# Button_Pad_Breakout-v05.net
KiCad netlist of a schematic drawn in Altium Designer
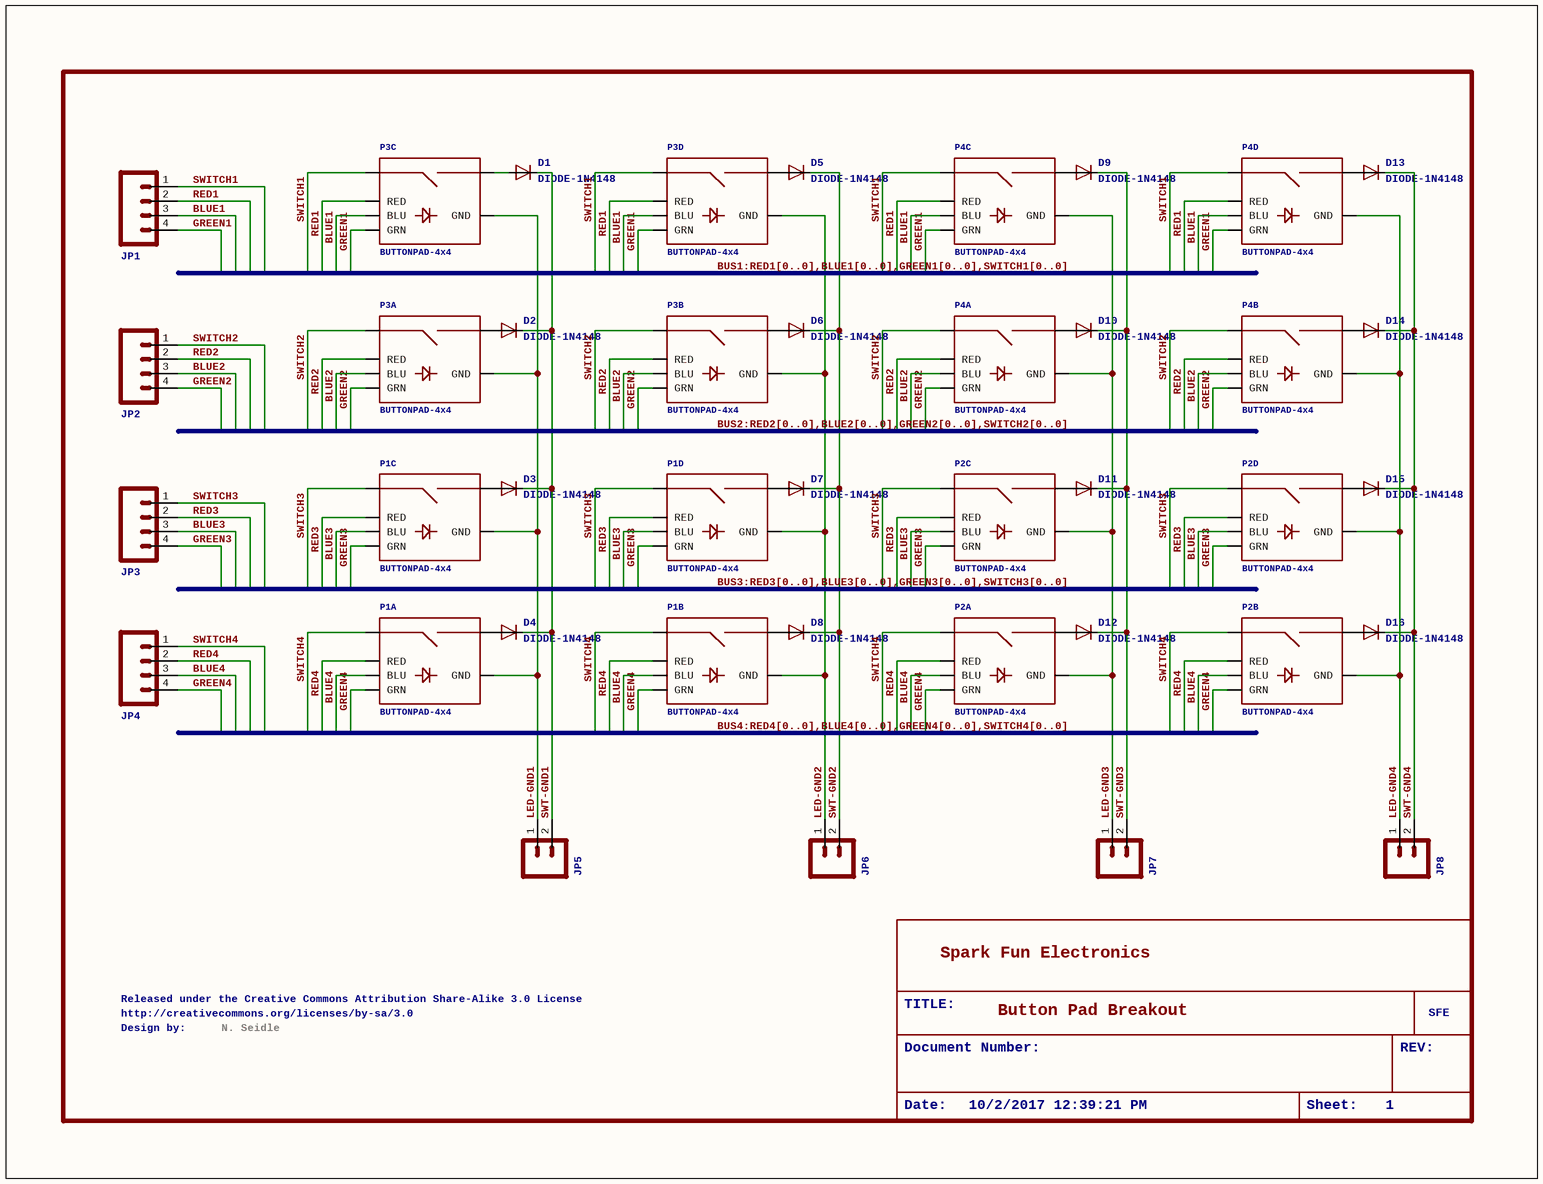
[diagram p0: Button_Pad_Breakout-v05.SchDoc]

(export (version "E")
  (design (tool "Eeschema 10.0.6"))
  (components
    (comp (ref "D1")
      (value "DIODE-1N4148")
      (footprint "DOIDE-1N4148")
      (libsource (lib "SparkFun") (part "DIODE-1N4148"))
    )
    (comp (ref "D2")
      (value "DIODE-1N4148")
      (footprint "DOIDE-1N4148")
      (libsource (lib "SparkFun") (part "DIODE-1N4148"))
    )
    (comp (ref "D3")
      (value "DIODE-1N4148")
      (footprint "DOIDE-1N4148")
      (libsource (lib "SparkFun") (part "DIODE-1N4148"))
    )
    (comp (ref "D4")
      (value "DIODE-1N4148")
      (footprint "DOIDE-1N4148")
      (libsource (lib "SparkFun") (part "DIODE-1N4148"))
    )
    (comp (ref "D5")
      (value "DIODE-1N4148")
      (footprint "DOIDE-1N4148")
      (libsource (lib "SparkFun") (part "DIODE-1N4148"))
    )
    (comp (ref "D6")
      (value "DIODE-1N4148")
      (footprint "DOIDE-1N4148")
      (libsource (lib "SparkFun") (part "DIODE-1N4148"))
    )
    (comp (ref "D7")
      (value "DIODE-1N4148")
      (footprint "DOIDE-1N4148")
      (libsource (lib "SparkFun") (part "DIODE-1N4148"))
    )
    (comp (ref "D8")
      (value "DIODE-1N4148")
      (footprint "DOIDE-1N4148")
      (libsource (lib "SparkFun") (part "DIODE-1N4148"))
    )
    (comp (ref "D9")
      (value "DIODE-1N4148")
      (footprint "DOIDE-1N4148")
      (libsource (lib "SparkFun") (part "DIODE-1N4148"))
    )
    (comp (ref "D10")
      (value "DIODE-1N4148")
      (footprint "DOIDE-1N4148")
      (libsource (lib "SparkFun") (part "DIODE-1N4148"))
    )
    (comp (ref "D11")
      (value "DIODE-1N4148")
      (footprint "DOIDE-1N4148")
      (libsource (lib "SparkFun") (part "DIODE-1N4148"))
    )
    (comp (ref "D12")
      (value "DIODE-1N4148")
      (footprint "DOIDE-1N4148")
      (libsource (lib "SparkFun") (part "DIODE-1N4148"))
    )
    (comp (ref "D13")
      (value "DIODE-1N4148")
      (footprint "DOIDE-1N4148")
      (libsource (lib "SparkFun") (part "DIODE-1N4148"))
    )
    (comp (ref "D14")
      (value "DIODE-1N4148")
      (footprint "DOIDE-1N4148")
      (libsource (lib "SparkFun") (part "DIODE-1N4148"))
    )
    (comp (ref "D15")
      (value "DIODE-1N4148")
      (footprint "DOIDE-1N4148")
      (libsource (lib "SparkFun") (part "DIODE-1N4148"))
    )
    (comp (ref "D16")
      (value "DIODE-1N4148")
      (footprint "DOIDE-1N4148")
      (libsource (lib "SparkFun") (part "DIODE-1N4148"))
    )
    (comp (ref "JP1")
      (value "M04POLAR")
      (footprint "MOLEX-1X4")
      (libsource (lib "SparkFun") (part "M04POLAR"))
    )
    (comp (ref "JP2")
      (value "M04POLAR")
      (footprint "MOLEX-1X4")
      (libsource (lib "SparkFun") (part "M04POLAR"))
    )
    (comp (ref "JP3")
      (value "M04POLAR")
      (footprint "MOLEX-1X4")
      (libsource (lib "SparkFun") (part "M04POLAR"))
    )
    (comp (ref "JP4")
      (value "M04POLAR")
      (footprint "MOLEX-1X4")
      (libsource (lib "SparkFun") (part "M04POLAR"))
    )
    (comp (ref "JP5")
      (value "M02POLAR")
      (footprint "MOLEX-1X2")
      (libsource (lib "SparkFun") (part "M02POLAR"))
    )
    (comp (ref "JP6")
      (value "M02POLAR")
      (footprint "MOLEX-1X2")
      (libsource (lib "SparkFun") (part "M02POLAR"))
    )
    (comp (ref "JP7")
      (value "M02POLAR")
      (footprint "MOLEX-1X2")
      (libsource (lib "SparkFun") (part "M02POLAR"))
    )
    (comp (ref "JP8")
      (value "M02POLAR")
      (footprint "MOLEX-1X2")
      (libsource (lib "SparkFun") (part "M02POLAR"))
    )
    (comp (ref "P1")
      (value "BUTTONPAD-4x4")
      (footprint "BUTTONPAD-2X2")
      (libsource (lib "SparkFun") (part "BUTTONPAD-2X2"))
    )
    (comp (ref "P2")
      (value "BUTTONPAD-4x4")
      (footprint "BUTTONPAD-2X2")
      (libsource (lib "SparkFun") (part "BUTTONPAD-2X2"))
    )
    (comp (ref "P3")
      (value "BUTTONPAD-4x4")
      (footprint "BUTTONPAD-2X2")
      (libsource (lib "SparkFun") (part "BUTTONPAD-2X2"))
    )
    (comp (ref "P4")
      (value "BUTTONPAD-4x4")
      (footprint "BUTTONPAD-2X2")
      (libsource (lib "SparkFun") (part "BUTTONPAD-2X2"))
    )
    (comp (ref "U$1")
      (value "LOGO-SFE")
      (footprint "SFE-NEW-WEBLOGO")
      (description "Spark Fun Electronics PCB LogoThis is the standard Spark Fun Electronics PCB logo.")
      (fields (field (name "SFE") "SFE"))
      (libsource (lib "SparkFun") (part "LOGO-SFE"))
    )
    (comp (ref "U$2")
      (value "CREATIVE_COMMONS")
      (footprint "CREATIVE_COMMONS")
      (fields
        (field (name "RELEASEDUNDERTHECREATIVECOMMONSATTRIBUTIONSHARE-ALIKE3.0LICENSE") "Released under the Creative Commons Attribution Share-Alike 3.0 License")
        (field (name "HTTP://CREATIVECOMMONS.ORG/LICENSES/BY-SA/3.0") "http://creativecommons.org/licenses/by-sa/3.0")
        (field (name "DESIGNBY") "Design by:")
      )
      (libsource (lib "SparkFun") (part "CREATIVE_COMMONS"))
    )
  )
  (nets
    (net (code "5") (name "/BLUE1") (class "Default")
      (node (ref "JP1") (pin "3") (pinfunction "3_3") (pintype "passive"))
      (node (ref "P3") (pin "BLU3") (pinfunction "BLU_BLU3") (pintype "passive"))
      (node (ref "P3") (pin "BLU4") (pinfunction "BLU_BLU4") (pintype "passive"))
      (node (ref "P4") (pin "BLU3") (pinfunction "BLU_BLU3") (pintype "passive"))
      (node (ref "P4") (pin "BLU4") (pinfunction "BLU_BLU4") (pintype "passive"))
    )
    (net (code "6") (name "/BLUE2") (class "Default")
      (node (ref "JP2") (pin "3") (pinfunction "3_3") (pintype "passive"))
      (node (ref "P3") (pin "BLU1") (pinfunction "BLU_BLU1") (pintype "passive"))
      (node (ref "P3") (pin "BLU2") (pinfunction "BLU_BLU2") (pintype "passive"))
      (node (ref "P4") (pin "BLU1") (pinfunction "BLU_BLU1") (pintype "passive"))
      (node (ref "P4") (pin "BLU2") (pinfunction "BLU_BLU2") (pintype "passive"))
    )
    (net (code "7") (name "/BLUE3") (class "Default")
      (node (ref "JP3") (pin "3") (pinfunction "3_3") (pintype "passive"))
      (node (ref "P1") (pin "BLU3") (pinfunction "BLU_BLU3") (pintype "passive"))
      (node (ref "P1") (pin "BLU4") (pinfunction "BLU_BLU4") (pintype "passive"))
      (node (ref "P2") (pin "BLU3") (pinfunction "BLU_BLU3") (pintype "passive"))
      (node (ref "P2") (pin "BLU4") (pinfunction "BLU_BLU4") (pintype "passive"))
    )
    (net (code "8") (name "/BLUE4") (class "Default")
      (node (ref "JP4") (pin "3") (pinfunction "3_3") (pintype "passive"))
      (node (ref "P1") (pin "BLU1") (pinfunction "BLU_BLU1") (pintype "passive"))
      (node (ref "P1") (pin "BLU2") (pinfunction "BLU_BLU2") (pintype "passive"))
      (node (ref "P2") (pin "BLU1") (pinfunction "BLU_BLU1") (pintype "passive"))
      (node (ref "P2") (pin "BLU2") (pinfunction "BLU_BLU2") (pintype "passive"))
    )
    (net (code "9") (name "/GREEN1") (class "Default")
      (node (ref "JP1") (pin "4") (pinfunction "4_4") (pintype "passive"))
      (node (ref "P3") (pin "GRN3") (pinfunction "GRN_GRN3") (pintype "passive"))
      (node (ref "P3") (pin "GRN4") (pinfunction "GRN_GRN4") (pintype "passive"))
      (node (ref "P4") (pin "GRN3") (pinfunction "GRN_GRN3") (pintype "passive"))
      (node (ref "P4") (pin "GRN4") (pinfunction "GRN_GRN4") (pintype "passive"))
    )
    (net (code "10") (name "/GREEN2") (class "Default")
      (node (ref "JP2") (pin "4") (pinfunction "4_4") (pintype "passive"))
      (node (ref "P3") (pin "GRN1") (pinfunction "GRN_GRN1") (pintype "passive"))
      (node (ref "P3") (pin "GRN2") (pinfunction "GRN_GRN2") (pintype "passive"))
      (node (ref "P4") (pin "GRN1") (pinfunction "GRN_GRN1") (pintype "passive"))
      (node (ref "P4") (pin "GRN2") (pinfunction "GRN_GRN2") (pintype "passive"))
    )
    (net (code "11") (name "/GREEN3") (class "Default")
      (node (ref "JP3") (pin "4") (pinfunction "4_4") (pintype "passive"))
      (node (ref "P1") (pin "GRN3") (pinfunction "GRN_GRN3") (pintype "passive"))
      (node (ref "P1") (pin "GRN4") (pinfunction "GRN_GRN4") (pintype "passive"))
      (node (ref "P2") (pin "GRN3") (pinfunction "GRN_GRN3") (pintype "passive"))
      (node (ref "P2") (pin "GRN4") (pinfunction "GRN_GRN4") (pintype "passive"))
    )
    (net (code "12") (name "/GREEN4") (class "Default")
      (node (ref "JP4") (pin "4") (pinfunction "4_4") (pintype "passive"))
      (node (ref "P1") (pin "GRN1") (pinfunction "GRN_GRN1") (pintype "passive"))
      (node (ref "P1") (pin "GRN2") (pinfunction "GRN_GRN2") (pintype "passive"))
      (node (ref "P2") (pin "GRN1") (pinfunction "GRN_GRN1") (pintype "passive"))
      (node (ref "P2") (pin "GRN2") (pinfunction "GRN_GRN2") (pintype "passive"))
    )
    (net (code "13") (name "/LED-GND1") (class "Default")
      (node (ref "JP5") (pin "1") (pinfunction "1_1") (pintype "passive"))
      (node (ref "P1") (pin "GND1") (pinfunction "GND_GND1") (pintype "passive"))
      (node (ref "P1") (pin "GND3") (pinfunction "GND_GND3") (pintype "passive"))
      (node (ref "P3") (pin "GND1") (pinfunction "GND_GND1") (pintype "passive"))
      (node (ref "P3") (pin "GND3") (pinfunction "GND_GND3") (pintype "passive"))
    )
    (net (code "14") (name "/LED-GND2") (class "Default")
      (node (ref "JP6") (pin "1") (pinfunction "1_1") (pintype "passive"))
      (node (ref "P1") (pin "GND2") (pinfunction "GND_GND2") (pintype "passive"))
      (node (ref "P1") (pin "GND4") (pinfunction "GND_GND4") (pintype "passive"))
      (node (ref "P3") (pin "GND2") (pinfunction "GND_GND2") (pintype "passive"))
      (node (ref "P3") (pin "GND4") (pinfunction "GND_GND4") (pintype "passive"))
    )
    (net (code "15") (name "/LED-GND3") (class "Default")
      (node (ref "JP7") (pin "1") (pinfunction "1_1") (pintype "passive"))
      (node (ref "P2") (pin "GND1") (pinfunction "GND_GND1") (pintype "passive"))
      (node (ref "P2") (pin "GND3") (pinfunction "GND_GND3") (pintype "passive"))
      (node (ref "P4") (pin "GND1") (pinfunction "GND_GND1") (pintype "passive"))
      (node (ref "P4") (pin "GND3") (pinfunction "GND_GND3") (pintype "passive"))
    )
    (net (code "16") (name "/LED-GND4") (class "Default")
      (node (ref "JP8") (pin "1") (pinfunction "1_1") (pintype "passive"))
      (node (ref "P2") (pin "GND2") (pinfunction "GND_GND2") (pintype "passive"))
      (node (ref "P2") (pin "GND4") (pinfunction "GND_GND4") (pintype "passive"))
      (node (ref "P4") (pin "GND2") (pinfunction "GND_GND2") (pintype "passive"))
      (node (ref "P4") (pin "GND4") (pinfunction "GND_GND4") (pintype "passive"))
    )
    (net (code "17") (name "/RED1") (class "Default")
      (node (ref "JP1") (pin "2") (pinfunction "2_2") (pintype "passive"))
      (node (ref "P3") (pin "RED3") (pinfunction "RED_RED3") (pintype "passive"))
      (node (ref "P3") (pin "RED4") (pinfunction "RED_RED4") (pintype "passive"))
      (node (ref "P4") (pin "RED3") (pinfunction "RED_RED3") (pintype "passive"))
      (node (ref "P4") (pin "RED4") (pinfunction "RED_RED4") (pintype "passive"))
    )
    (net (code "18") (name "/RED2") (class "Default")
      (node (ref "JP2") (pin "2") (pinfunction "2_2") (pintype "passive"))
      (node (ref "P3") (pin "RED1") (pinfunction "RED_RED1") (pintype "passive"))
      (node (ref "P3") (pin "RED2") (pinfunction "RED_RED2") (pintype "passive"))
      (node (ref "P4") (pin "RED1") (pinfunction "RED_RED1") (pintype "passive"))
      (node (ref "P4") (pin "RED2") (pinfunction "RED_RED2") (pintype "passive"))
    )
    (net (code "19") (name "/RED3") (class "Default")
      (node (ref "JP3") (pin "2") (pinfunction "2_2") (pintype "passive"))
      (node (ref "P1") (pin "RED3") (pinfunction "RED_RED3") (pintype "passive"))
      (node (ref "P1") (pin "RED4") (pinfunction "RED_RED4") (pintype "passive"))
      (node (ref "P2") (pin "RED3") (pinfunction "RED_RED3") (pintype "passive"))
      (node (ref "P2") (pin "RED4") (pinfunction "RED_RED4") (pintype "passive"))
    )
    (net (code "20") (name "/RED4") (class "Default")
      (node (ref "JP4") (pin "2") (pinfunction "2_2") (pintype "passive"))
      (node (ref "P1") (pin "RED1") (pinfunction "RED_RED1") (pintype "passive"))
      (node (ref "P1") (pin "RED2") (pinfunction "RED_RED2") (pintype "passive"))
      (node (ref "P2") (pin "RED1") (pinfunction "RED_RED1") (pintype "passive"))
      (node (ref "P2") (pin "RED2") (pinfunction "RED_RED2") (pintype "passive"))
    )
    (net (code "21") (name "/SWITCH1") (class "Default")
      (node (ref "JP1") (pin "1") (pinfunction "1_1") (pintype "passive"))
      (node (ref "P3") (pin "SIG5") (pinfunction "SIG1_SIG5") (pintype "passive"))
      (node (ref "P3") (pin "SIG7") (pinfunction "SIG1_SIG7") (pintype "passive"))
      (node (ref "P4") (pin "SIG5") (pinfunction "SIG1_SIG5") (pintype "passive"))
      (node (ref "P4") (pin "SIG7") (pinfunction "SIG1_SIG7") (pintype "passive"))
    )
    (net (code "22") (name "/SWITCH2") (class "Default")
      (node (ref "JP2") (pin "1") (pinfunction "1_1") (pintype "passive"))
      (node (ref "P3") (pin "SIG1") (pinfunction "SIG1_SIG1") (pintype "passive"))
      (node (ref "P3") (pin "SIG3") (pinfunction "SIG1_SIG3") (pintype "passive"))
      (node (ref "P4") (pin "SIG1") (pinfunction "SIG1_SIG1") (pintype "passive"))
      (node (ref "P4") (pin "SIG3") (pinfunction "SIG1_SIG3") (pintype "passive"))
    )
    (net (code "23") (name "/SWITCH3") (class "Default")
      (node (ref "JP3") (pin "1") (pinfunction "1_1") (pintype "passive"))
      (node (ref "P1") (pin "SIG5") (pinfunction "SIG1_SIG5") (pintype "passive"))
      (node (ref "P1") (pin "SIG7") (pinfunction "SIG1_SIG7") (pintype "passive"))
      (node (ref "P2") (pin "SIG5") (pinfunction "SIG1_SIG5") (pintype "passive"))
      (node (ref "P2") (pin "SIG7") (pinfunction "SIG1_SIG7") (pintype "passive"))
    )
    (net (code "24") (name "/SWITCH4") (class "Default")
      (node (ref "JP4") (pin "1") (pinfunction "1_1") (pintype "passive"))
      (node (ref "P1") (pin "SIG1") (pinfunction "SIG1_SIG1") (pintype "passive"))
      (node (ref "P1") (pin "SIG3") (pinfunction "SIG1_SIG3") (pintype "passive"))
      (node (ref "P2") (pin "SIG1") (pinfunction "SIG1_SIG1") (pintype "passive"))
      (node (ref "P2") (pin "SIG3") (pinfunction "SIG1_SIG3") (pintype "passive"))
    )
    (net (code "25") (name "/SWT-GND1") (class "Default")
      (node (ref "D1") (pin "P$2") (pinfunction "C_P$2") (pintype "passive"))
      (node (ref "D2") (pin "P$2") (pinfunction "C_P$2") (pintype "passive"))
      (node (ref "D3") (pin "P$2") (pinfunction "C_P$2") (pintype "passive"))
      (node (ref "D4") (pin "P$2") (pinfunction "C_P$2") (pintype "passive"))
      (node (ref "JP5") (pin "2") (pinfunction "2_2") (pintype "passive"))
    )
    (net (code "26") (name "/SWT-GND2") (class "Default")
      (node (ref "D5") (pin "P$2") (pinfunction "C_P$2") (pintype "passive"))
      (node (ref "D6") (pin "P$2") (pinfunction "C_P$2") (pintype "passive"))
      (node (ref "D7") (pin "P$2") (pinfunction "C_P$2") (pintype "passive"))
      (node (ref "D8") (pin "P$2") (pinfunction "C_P$2") (pintype "passive"))
      (node (ref "JP6") (pin "2") (pinfunction "2_2") (pintype "passive"))
    )
    (net (code "27") (name "/SWT-GND3") (class "Default")
      (node (ref "D10") (pin "P$2") (pinfunction "C_P$2") (pintype "passive"))
      (node (ref "D11") (pin "P$2") (pinfunction "C_P$2") (pintype "passive"))
      (node (ref "D12") (pin "P$2") (pinfunction "C_P$2") (pintype "passive"))
      (node (ref "D9") (pin "P$2") (pinfunction "C_P$2") (pintype "passive"))
      (node (ref "JP7") (pin "2") (pinfunction "2_2") (pintype "passive"))
    )
    (net (code "28") (name "/SWT-GND4") (class "Default")
      (node (ref "D13") (pin "P$2") (pinfunction "C_P$2") (pintype "passive"))
      (node (ref "D14") (pin "P$2") (pinfunction "C_P$2") (pintype "passive"))
      (node (ref "D15") (pin "P$2") (pinfunction "C_P$2") (pintype "passive"))
      (node (ref "D16") (pin "P$2") (pinfunction "C_P$2") (pintype "passive"))
      (node (ref "JP8") (pin "2") (pinfunction "2_2") (pintype "passive"))
    )
    (net (code "33") (name "Net-(D1-A)") (class "Default")
      (node (ref "D1") (pin "P$1") (pinfunction "A_P$1") (pintype "passive"))
      (node (ref "P3") (pin "SIG6") (pinfunction "SIG2_SIG6") (pintype "passive"))
    )
    (net (code "34") (name "Net-(D2-A)") (class "Default")
      (node (ref "D2") (pin "P$1") (pinfunction "A_P$1") (pintype "passive"))
      (node (ref "P3") (pin "SIG2") (pinfunction "SIG2_SIG2") (pintype "passive"))
    )
    (net (code "35") (name "Net-(D3-A)") (class "Default")
      (node (ref "D3") (pin "P$1") (pinfunction "A_P$1") (pintype "passive"))
      (node (ref "P1") (pin "SIG6") (pinfunction "SIG2_SIG6") (pintype "passive"))
    )
    (net (code "36") (name "Net-(D4-A)") (class "Default")
      (node (ref "D4") (pin "P$1") (pinfunction "A_P$1") (pintype "passive"))
      (node (ref "P1") (pin "SIG2") (pinfunction "SIG2_SIG2") (pintype "passive"))
    )
    (net (code "37") (name "Net-(D5-A)") (class "Default")
      (node (ref "D5") (pin "P$1") (pinfunction "A_P$1") (pintype "passive"))
      (node (ref "P3") (pin "SIG8") (pinfunction "SIG2_SIG8") (pintype "passive"))
    )
    (net (code "38") (name "Net-(D6-A)") (class "Default")
      (node (ref "D6") (pin "P$1") (pinfunction "A_P$1") (pintype "passive"))
      (node (ref "P3") (pin "SIG4") (pinfunction "SIG2_SIG4") (pintype "passive"))
    )
    (net (code "39") (name "Net-(D7-A)") (class "Default")
      (node (ref "D7") (pin "P$1") (pinfunction "A_P$1") (pintype "passive"))
      (node (ref "P1") (pin "SIG8") (pinfunction "SIG2_SIG8") (pintype "passive"))
    )
    (net (code "40") (name "Net-(D8-A)") (class "Default")
      (node (ref "D8") (pin "P$1") (pinfunction "A_P$1") (pintype "passive"))
      (node (ref "P1") (pin "SIG4") (pinfunction "SIG2_SIG4") (pintype "passive"))
    )
    (net (code "41") (name "Net-(D9-A)") (class "Default")
      (node (ref "D9") (pin "P$1") (pinfunction "A_P$1") (pintype "passive"))
      (node (ref "P4") (pin "SIG6") (pinfunction "SIG2_SIG6") (pintype "passive"))
    )
    (net (code "42") (name "Net-(D10-A)") (class "Default")
      (node (ref "D10") (pin "P$1") (pinfunction "A_P$1") (pintype "passive"))
      (node (ref "P4") (pin "SIG2") (pinfunction "SIG2_SIG2") (pintype "passive"))
    )
    (net (code "43") (name "Net-(D11-A)") (class "Default")
      (node (ref "D11") (pin "P$1") (pinfunction "A_P$1") (pintype "passive"))
      (node (ref "P2") (pin "SIG6") (pinfunction "SIG2_SIG6") (pintype "passive"))
    )
    (net (code "44") (name "Net-(D12-A)") (class "Default")
      (node (ref "D12") (pin "P$1") (pinfunction "A_P$1") (pintype "passive"))
      (node (ref "P2") (pin "SIG2") (pinfunction "SIG2_SIG2") (pintype "passive"))
    )
    (net (code "45") (name "Net-(D13-A)") (class "Default")
      (node (ref "D13") (pin "P$1") (pinfunction "A_P$1") (pintype "passive"))
      (node (ref "P4") (pin "SIG8") (pinfunction "SIG2_SIG8") (pintype "passive"))
    )
    (net (code "46") (name "Net-(D14-A)") (class "Default")
      (node (ref "D14") (pin "P$1") (pinfunction "A_P$1") (pintype "passive"))
      (node (ref "P4") (pin "SIG4") (pinfunction "SIG2_SIG4") (pintype "passive"))
    )
    (net (code "47") (name "Net-(D15-A)") (class "Default")
      (node (ref "D15") (pin "P$1") (pinfunction "A_P$1") (pintype "passive"))
      (node (ref "P2") (pin "SIG8") (pinfunction "SIG2_SIG8") (pintype "passive"))
    )
    (net (code "48") (name "Net-(D16-A)") (class "Default")
      (node (ref "D16") (pin "P$1") (pinfunction "A_P$1") (pintype "passive"))
      (node (ref "P2") (pin "SIG4") (pinfunction "SIG2_SIG4") (pintype "passive"))
    )
  )
)
